# PowerConvert.net
KiCad netlist of a schematic drawn in Altium Designer
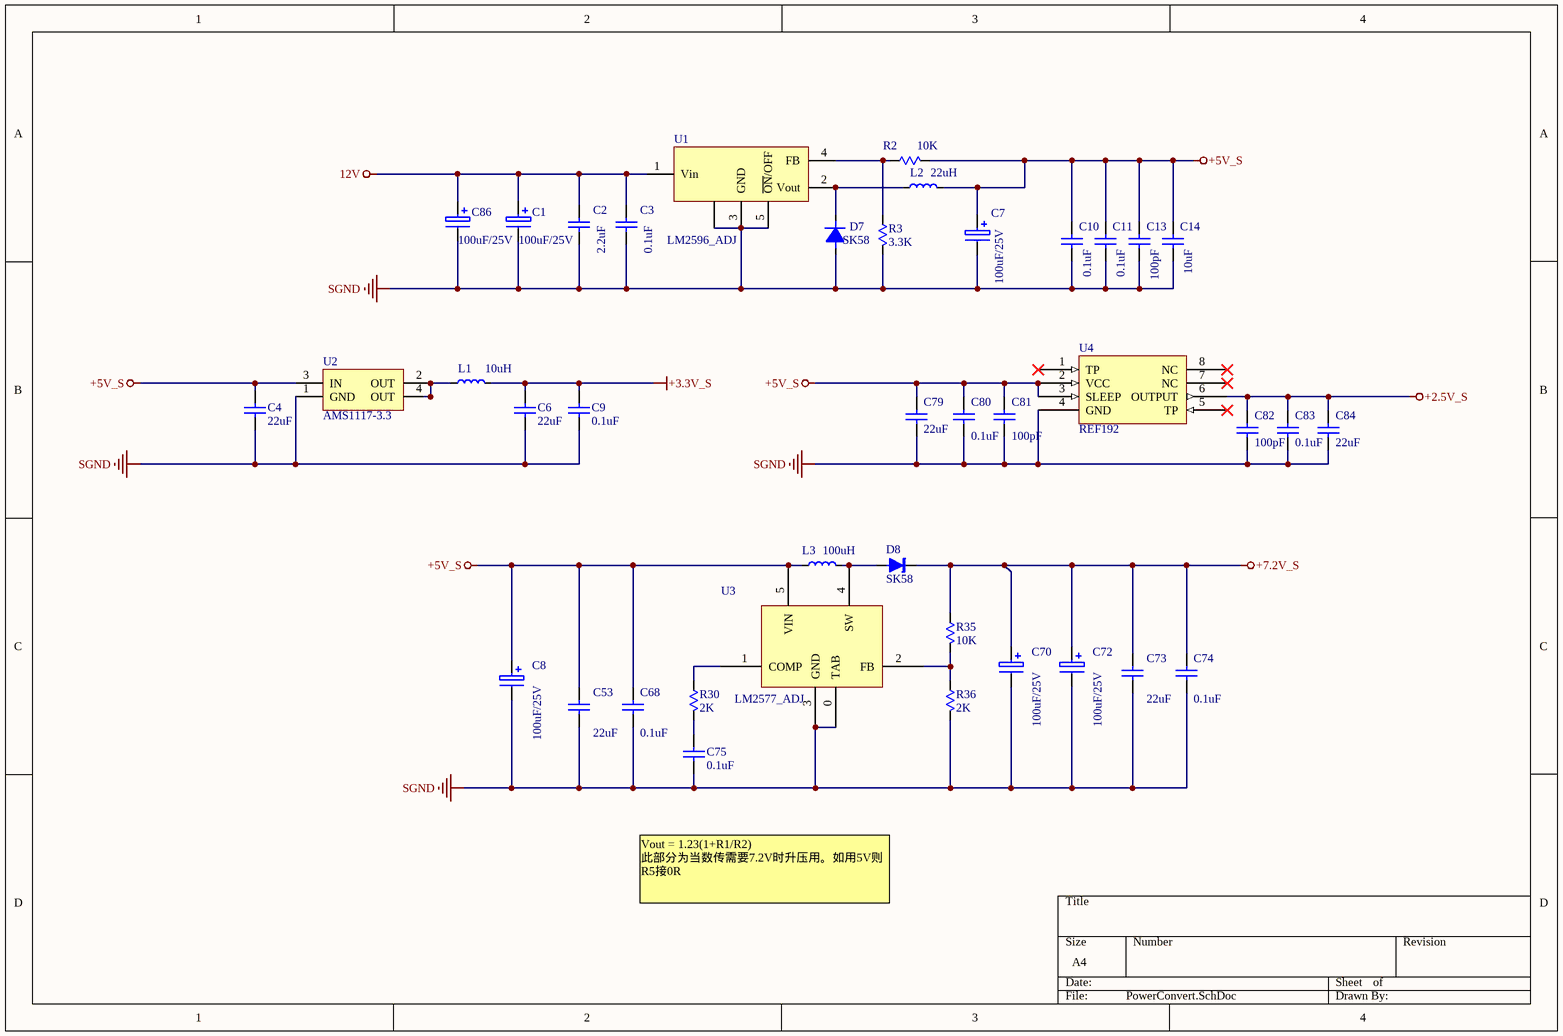
[diagram p0: PowerConvert.SchDoc]

(export (version "E")
  (design (tool "Eeschema 10.0.6"))
  (components
    (comp (ref "C1")
      (value "100uF/25V")
      (footprint "CT7343-E-S")
      (description "Electrolytic Capacitor")
      (libsource (lib "*") (part "ELECTRO"))
    )
    (comp (ref "C2")
      (value "2.2uF")
      (footprint "C1206")
      (description "CAP")
      (fields (field (name "PUBLISHER") "Altium Limited"))
      (libsource (lib "Passive Components Class") (part "CAP"))
    )
    (comp (ref "C3")
      (value "0.1uF")
      (footprint "C0805")
      (description "CAP")
      (fields (field (name "PUBLISHER") "Altium Limited"))
      (libsource (lib "Passive Components Class") (part "CAP"))
    )
    (comp (ref "C4")
      (value "22uF")
      (footprint "C1206")
      (description "CAP")
      (fields (field (name "PUBLISHER") "Altium Limited"))
      (libsource (lib "Passive Components Class") (part "CAP"))
    )
    (comp (ref "C6")
      (value "22uF")
      (footprint "C1206")
      (description "CAP")
      (fields (field (name "PUBLISHER") "Altium Limited"))
      (libsource (lib "Passive Components Class") (part "CAP"))
    )
    (comp (ref "C7")
      (value "100uF/25V")
      (footprint "CT7343-E-S")
      (description "Electrolytic Capacitor")
      (libsource (lib "*") (part "ELECTRO"))
    )
    (comp (ref "C8")
      (value "100uF/25V")
      (footprint "CT7343-E-S")
      (description "Electrolytic Capacitor")
      (libsource (lib "*") (part "ELECTRO"))
    )
    (comp (ref "C9")
      (value "0.1uF")
      (footprint "C0805")
      (description "CAP")
      (fields (field (name "PUBLISHER") "Altium Limited"))
      (libsource (lib "Passive Components Class") (part "CAP"))
    )
    (comp (ref "C10")
      (value "0.1uF")
      (footprint "C0805")
      (description "CAP")
      (fields (field (name "PUBLISHER") "Altium Limited"))
      (libsource (lib "Passive Components Class") (part "CAP"))
    )
    (comp (ref "C11")
      (value "0.1uF")
      (footprint "C0805")
      (description "CAP")
      (fields (field (name "PUBLISHER") "Altium Limited"))
      (libsource (lib "Passive Components Class") (part "CAP"))
    )
    (comp (ref "C13")
      (value "100pF")
      (footprint "C0805")
      (description "CAP")
      (fields (field (name "PUBLISHER") "Altium Limited"))
      (libsource (lib "Passive Components Class") (part "CAP"))
    )
    (comp (ref "C14")
      (value "10uF")
      (footprint "C0805")
      (description "CAP")
      (fields (field (name "PUBLISHER") "Altium Limited"))
      (libsource (lib "Passive Components Class") (part "CAP"))
    )
    (comp (ref "C53")
      (value "22uF")
      (footprint "C1206")
      (description "CAP")
      (fields (field (name "PUBLISHER") "Altium Limited"))
      (libsource (lib "Passive Components Class") (part "CAP"))
    )
    (comp (ref "C68")
      (value "0.1uF")
      (footprint "C0805")
      (description "CAP")
      (fields (field (name "PUBLISHER") "Altium Limited"))
      (libsource (lib "Passive Components Class") (part "CAP"))
    )
    (comp (ref "C70")
      (value "100uF/25V")
      (footprint "CT7343-E-S")
      (description "Electrolytic Capacitor")
      (libsource (lib "*") (part "ELECTRO"))
    )
    (comp (ref "C72")
      (value "100uF/25V")
      (footprint "CT7343-E-S")
      (description "Electrolytic Capacitor")
      (libsource (lib "*") (part "ELECTRO"))
    )
    (comp (ref "C73")
      (value "22uF")
      (footprint "C1206")
      (description "CAP")
      (fields (field (name "PUBLISHER") "Altium Limited"))
      (libsource (lib "Passive Components Class") (part "CAP"))
    )
    (comp (ref "C74")
      (value "0.1uF")
      (footprint "C0805")
      (description "CAP")
      (fields (field (name "PUBLISHER") "Altium Limited"))
      (libsource (lib "Passive Components Class") (part "CAP"))
    )
    (comp (ref "C75")
      (value "0.1uF")
      (footprint "C0805")
      (description "CAP")
      (fields (field (name "PUBLISHER") "Altium Limited"))
      (libsource (lib "Passive Components Class") (part "CAP"))
    )
    (comp (ref "C79")
      (value "22uF")
      (footprint "C1206")
      (description "CAP")
      (fields (field (name "PUBLISHER") "Altium Limited"))
      (libsource (lib "Passive Components Class") (part "CAP"))
    )
    (comp (ref "C80")
      (value "0.1uF")
      (footprint "C0805")
      (description "CAP")
      (fields (field (name "PUBLISHER") "Altium Limited"))
      (libsource (lib "Passive Components Class") (part "CAP"))
    )
    (comp (ref "C81")
      (value "100pF")
      (footprint "C0805")
      (description "CAP")
      (fields (field (name "PUBLISHER") "Altium Limited"))
      (libsource (lib "Passive Components Class") (part "CAP"))
    )
    (comp (ref "C82")
      (value "100pF")
      (footprint "C0805")
      (description "CAP")
      (fields (field (name "PUBLISHER") "Altium Limited"))
      (libsource (lib "Passive Components Class") (part "CAP"))
    )
    (comp (ref "C83")
      (value "0.1uF")
      (footprint "C0805")
      (description "CAP")
      (fields (field (name "PUBLISHER") "Altium Limited"))
      (libsource (lib "Passive Components Class") (part "CAP"))
    )
    (comp (ref "C84")
      (value "22uF")
      (footprint "C1206")
      (description "CAP")
      (fields (field (name "PUBLISHER") "Altium Limited"))
      (libsource (lib "Passive Components Class") (part "CAP"))
    )
    (comp (ref "C86")
      (value "100uF/25V")
      (footprint "CT7343-E-S")
      (description "Electrolytic Capacitor")
      (libsource (lib "*") (part "ELECTRO"))
    )
    (comp (ref "D7")
      (value "SK58")
      (footprint "SMB")
      (description "Diode")
      (libsource (lib "*") (part "DIODE1"))
    )
    (comp (ref "D8")
      (value "SK58")
      (footprint "SMB")
      (description "Schottky barrier rectifier")
      (libsource (lib "Passive Components Class") (part "DIODE-SCHOTTKY"))
    )
    (comp (ref "L1")
      (value "10uH")
      (footprint "L0805-C")
      (description "INDUCTOR")
      (fields (field (name "PUBLISHER") "Altium Limited"))
      (libsource (lib "") (part "INDUCTOR_1"))
    )
    (comp (ref "L2")
      (value "22uH")
      (footprint "L5050-P")
      (description "INDUCTOR")
      (fields (field (name "PUBLISHER") "Altium Limited"))
      (libsource (lib "") (part "INDUCTOR_1"))
    )
    (comp (ref "L3")
      (value "100uH")
      (footprint "L5050-P")
      (description "INDUCTOR")
      (fields (field (name "PUBLISHER") "Altium Limited"))
      (libsource (lib "Passive Components Class") (part "INDUCTOR"))
    )
    (comp (ref "R2")
      (value "10K")
      (footprint "R0805")
      (description "Resistor")
      (fields (field (name "PUBLISHER") "Altium Limited"))
      (libsource (lib "Passive Components Class") (part "RES"))
    )
    (comp (ref "R3")
      (value "3.3K")
      (footprint "R0805")
      (description "Resistor")
      (fields (field (name "PUBLISHER") "Altium Limited"))
      (libsource (lib "Passive Components Class") (part "RES"))
    )
    (comp (ref "R30")
      (value "2K")
      (footprint "R0805")
      (description "Resistor")
      (fields (field (name "PUBLISHER") "Altium Limited"))
      (libsource (lib "Passive Components Class") (part "RES"))
    )
    (comp (ref "R35")
      (value "10K")
      (footprint "R0805")
      (description "Resistor")
      (fields (field (name "PUBLISHER") "Altium Limited"))
      (libsource (lib "Passive Components Class") (part "RES"))
    )
    (comp (ref "R36")
      (value "2K")
      (footprint "R0805")
      (description "Resistor")
      (fields (field (name "PUBLISHER") "Altium Limited"))
      (libsource (lib "Passive Components Class") (part "RES"))
    )
    (comp (ref "U1") (value "LM2596_ADJ") (footprint "TO263") (libsource (lib "*") (part "LM2575")))
    (comp (ref "U2")
      (value "AMS1117-3.3")
      (footprint "SOT-223")
      (description "800mA and 1A Low Dropout Positive Regulator 2.85V, 3.3V, 5V, and Adjustable")
      (fields (field (name "PUBLISHER") "Altium Limited"))
      (libsource (lib "BB Power Mgt Voltage Regulator") (part "REG1117-3.3"))
    )
    (comp (ref "U3")
      (value "LM2577_ADJ")
      (footprint "TO263")
      (libsource (lib "Power Management Class") (part "LM2577"))
    )
    (comp (ref "U4") (value "REF192") (footprint "SO-8") (libsource (lib "tribute") (part "REF192/5/7")))
  )
  (nets
    (net (code "1") (name "+2.5V_S") (class "Default")
      (node (ref "C82") (pin "2") (pinfunction "2_2") (pintype "passive"))
      (node (ref "C83") (pin "2") (pinfunction "2_2") (pintype "passive"))
      (node (ref "C84") (pin "2") (pinfunction "2_2") (pintype "passive"))
      (node (ref "U4") (pin "6") (pinfunction "OUTPUT_6") (pintype "output"))
    )
    (net (code "2") (name "+3.3V_S") (class "Default")
      (node (ref "C6") (pin "1") (pinfunction "1_1") (pintype "passive"))
      (node (ref "C9") (pin "2") (pinfunction "2_2") (pintype "passive"))
      (node (ref "L1") (pin "1") (pinfunction "1_1") (pintype "passive"))
    )
    (net (code "3") (name "+5V_S") (class "Default")
      (node (ref "C10") (pin "2") (pinfunction "2_2") (pintype "passive"))
      (node (ref "C11") (pin "2") (pinfunction "2_2") (pintype "passive"))
      (node (ref "C13") (pin "2") (pinfunction "2_2") (pintype "passive"))
      (node (ref "C14") (pin "2") (pinfunction "2_2") (pintype "passive"))
      (node (ref "C4") (pin "1") (pinfunction "1_1") (pintype "passive"))
      (node (ref "C53") (pin "1") (pinfunction "1_1") (pintype "passive"))
      (node (ref "C68") (pin "2") (pinfunction "2_2") (pintype "passive"))
      (node (ref "C7") (pin "1") (pinfunction "1_1") (pintype "passive"))
      (node (ref "C79") (pin "2") (pinfunction "2_2") (pintype "passive"))
      (node (ref "C8") (pin "1") (pinfunction "1_1") (pintype "passive"))
      (node (ref "C80") (pin "2") (pinfunction "2_2") (pintype "passive"))
      (node (ref "C81") (pin "2") (pinfunction "2_2") (pintype "passive"))
      (node (ref "L2") (pin "1") (pinfunction "1_1") (pintype "passive"))
      (node (ref "L3") (pin "1") (pinfunction "1_1") (pintype "passive"))
      (node (ref "R2") (pin "1") (pinfunction "1_1") (pintype "passive"))
      (node (ref "U2") (pin "3") (pinfunction "IN_3") (pintype "power_in"))
      (node (ref "U3") (pin "5") (pinfunction "VIN_5") (pintype "passive"))
      (node (ref "U4") (pin "2") (pinfunction "VCC_2") (pintype "input"))
      (node (ref "U4") (pin "3") (pinfunction "SLEEP_3") (pintype "input"))
    )
    (net (code "4") (name "+7.2V_S") (class "Default")
      (node (ref "C70") (pin "1") (pinfunction "1_1") (pintype "passive"))
      (node (ref "C72") (pin "1") (pinfunction "1_1") (pintype "passive"))
      (node (ref "C73") (pin "1") (pinfunction "1_1") (pintype "passive"))
      (node (ref "C74") (pin "2") (pinfunction "2_2") (pintype "passive"))
      (node (ref "D8") (pin "2") (pinfunction "K_2") (pintype "passive"))
      (node (ref "R35") (pin "1") (pinfunction "1_1") (pintype "passive"))
    )
    (net (code "5") (name "12V") (class "Default")
      (node (ref "C1") (pin "1") (pinfunction "1_1") (pintype "passive"))
      (node (ref "C2") (pin "2") (pinfunction "2_2") (pintype "passive"))
      (node (ref "C3") (pin "2") (pinfunction "2_2") (pintype "passive"))
      (node (ref "C86") (pin "1") (pinfunction "1_1") (pintype "passive"))
      (node (ref "U1") (pin "1") (pinfunction "Vin_1") (pintype "power_in"))
    )
    (net (code "6") (name "Net-(C75-Pad2)") (class "Default")
      (node (ref "C75") (pin "2") (pinfunction "2_2") (pintype "passive"))
      (node (ref "R30") (pin "2") (pinfunction "2_2") (pintype "passive"))
    )
    (net (code "7") (name "Net-(D7-K)") (class "Default")
      (node (ref "D7") (pin "2") (pinfunction "K_2") (pintype "passive"))
      (node (ref "L2") (pin "2") (pinfunction "2_2") (pintype "passive"))
      (node (ref "U1") (pin "2") (pinfunction "Vout_2") (pintype "power_in"))
    )
    (net (code "8") (name "Net-(D8-A)") (class "Default")
      (node (ref "D8") (pin "1") (pinfunction "A_1") (pintype "passive"))
      (node (ref "L3") (pin "2") (pinfunction "2_2") (pintype "passive"))
      (node (ref "U3") (pin "4") (pinfunction "SW_4") (pintype "passive"))
    )
    (net (code "9") (name "Net-(L1-Pad2)") (class "Default")
      (node (ref "L1") (pin "2") (pinfunction "2_2") (pintype "passive"))
      (node (ref "U2") (pin "2") (pinfunction "OUT_2") (pintype "power_in"))
      (node (ref "U2") (pin "4") (pinfunction "OUT_4") (pintype "power_in"))
    )
    (net (code "10") (name "Net-(U1-FB)") (class "Default")
      (node (ref "R2") (pin "2") (pinfunction "2_2") (pintype "passive"))
      (node (ref "R3") (pin "2") (pinfunction "2_2") (pintype "passive"))
      (node (ref "U1") (pin "4") (pinfunction "FB_4") (pintype "passive"))
    )
    (net (code "11") (name "Net-(U3-COMP)") (class "Default")
      (node (ref "R30") (pin "1") (pinfunction "1_1") (pintype "passive"))
      (node (ref "U3") (pin "1") (pinfunction "COMP_1") (pintype "passive"))
    )
    (net (code "12") (name "Net-(U3-FB)") (class "Default")
      (node (ref "R35") (pin "2") (pinfunction "2_2") (pintype "passive"))
      (node (ref "R36") (pin "1") (pinfunction "1_1") (pintype "passive"))
      (node (ref "U3") (pin "2") (pinfunction "FB_2") (pintype "passive"))
    )
    (net (code "13") (name "SGND") (class "Default")
      (node (ref "C1") (pin "2") (pinfunction "2_2") (pintype "passive"))
      (node (ref "C10") (pin "1") (pinfunction "1_1") (pintype "passive"))
      (node (ref "C11") (pin "1") (pinfunction "1_1") (pintype "passive"))
      (node (ref "C13") (pin "1") (pinfunction "1_1") (pintype "passive"))
      (node (ref "C14") (pin "1") (pinfunction "1_1") (pintype "passive"))
      (node (ref "C2") (pin "1") (pinfunction "1_1") (pintype "passive"))
      (node (ref "C3") (pin "1") (pinfunction "1_1") (pintype "passive"))
      (node (ref "C4") (pin "2") (pinfunction "2_2") (pintype "passive"))
      (node (ref "C53") (pin "2") (pinfunction "2_2") (pintype "passive"))
      (node (ref "C6") (pin "2") (pinfunction "2_2") (pintype "passive"))
      (node (ref "C68") (pin "1") (pinfunction "1_1") (pintype "passive"))
      (node (ref "C7") (pin "2") (pinfunction "2_2") (pintype "passive"))
      (node (ref "C70") (pin "2") (pinfunction "2_2") (pintype "passive"))
      (node (ref "C72") (pin "2") (pinfunction "2_2") (pintype "passive"))
      (node (ref "C73") (pin "2") (pinfunction "2_2") (pintype "passive"))
      (node (ref "C74") (pin "1") (pinfunction "1_1") (pintype "passive"))
      (node (ref "C75") (pin "1") (pinfunction "1_1") (pintype "passive"))
      (node (ref "C79") (pin "1") (pinfunction "1_1") (pintype "passive"))
      (node (ref "C8") (pin "2") (pinfunction "2_2") (pintype "passive"))
      (node (ref "C80") (pin "1") (pinfunction "1_1") (pintype "passive"))
      (node (ref "C81") (pin "1") (pinfunction "1_1") (pintype "passive"))
      (node (ref "C82") (pin "1") (pinfunction "1_1") (pintype "passive"))
      (node (ref "C83") (pin "1") (pinfunction "1_1") (pintype "passive"))
      (node (ref "C84") (pin "1") (pinfunction "1_1") (pintype "passive"))
      (node (ref "C86") (pin "2") (pinfunction "2_2") (pintype "passive"))
      (node (ref "C9") (pin "1") (pinfunction "1_1") (pintype "passive"))
      (node (ref "D7") (pin "1") (pinfunction "A_1") (pintype "passive"))
      (node (ref "R3") (pin "1") (pinfunction "1_1") (pintype "passive"))
      (node (ref "R36") (pin "2") (pinfunction "2_2") (pintype "passive"))
      (node (ref "U1") (pin "0") (pinfunction "GND_0") (pintype "passive"))
      (node (ref "U1") (pin "3") (pinfunction "GND_3") (pintype "power_in"))
      (node (ref "U1") (pin "5") (pinfunction "~{ON}/OFF_5") (pintype "passive"))
      (node (ref "U2") (pin "1") (pinfunction "GND_1") (pintype "power_in"))
      (node (ref "U3") (pin "0") (pinfunction "TAB_0") (pintype "passive"))
      (node (ref "U3") (pin "3") (pinfunction "GND_3") (pintype "passive"))
      (node (ref "U4") (pin "4") (pinfunction "GND_4") (pintype "power_in"))
    )
    (net (code "14") (name "unconnected-(U4-NC-Pad7)") (class "Default")
      (node (ref "U4") (pin "7") (pinfunction "NC_7") (pintype "passive+no_connect"))
    )
    (net (code "15") (name "unconnected-(U4-NC-Pad8)") (class "Default")
      (node (ref "U4") (pin "8") (pinfunction "NC_8") (pintype "passive+no_connect"))
    )
    (net (code "16") (name "unconnected-(U4-TP-Pad1)") (class "Default")
      (node (ref "U4") (pin "1") (pinfunction "TP_1") (pintype "input+no_connect"))
    )
    (net (code "17") (name "unconnected-(U4-TP-Pad5)") (class "Default")
      (node (ref "U4") (pin "5") (pinfunction "TP_5") (pintype "input+no_connect"))
    )
  )
)
